# MCU.net
KiCad netlist of a schematic drawn in Altium Designer
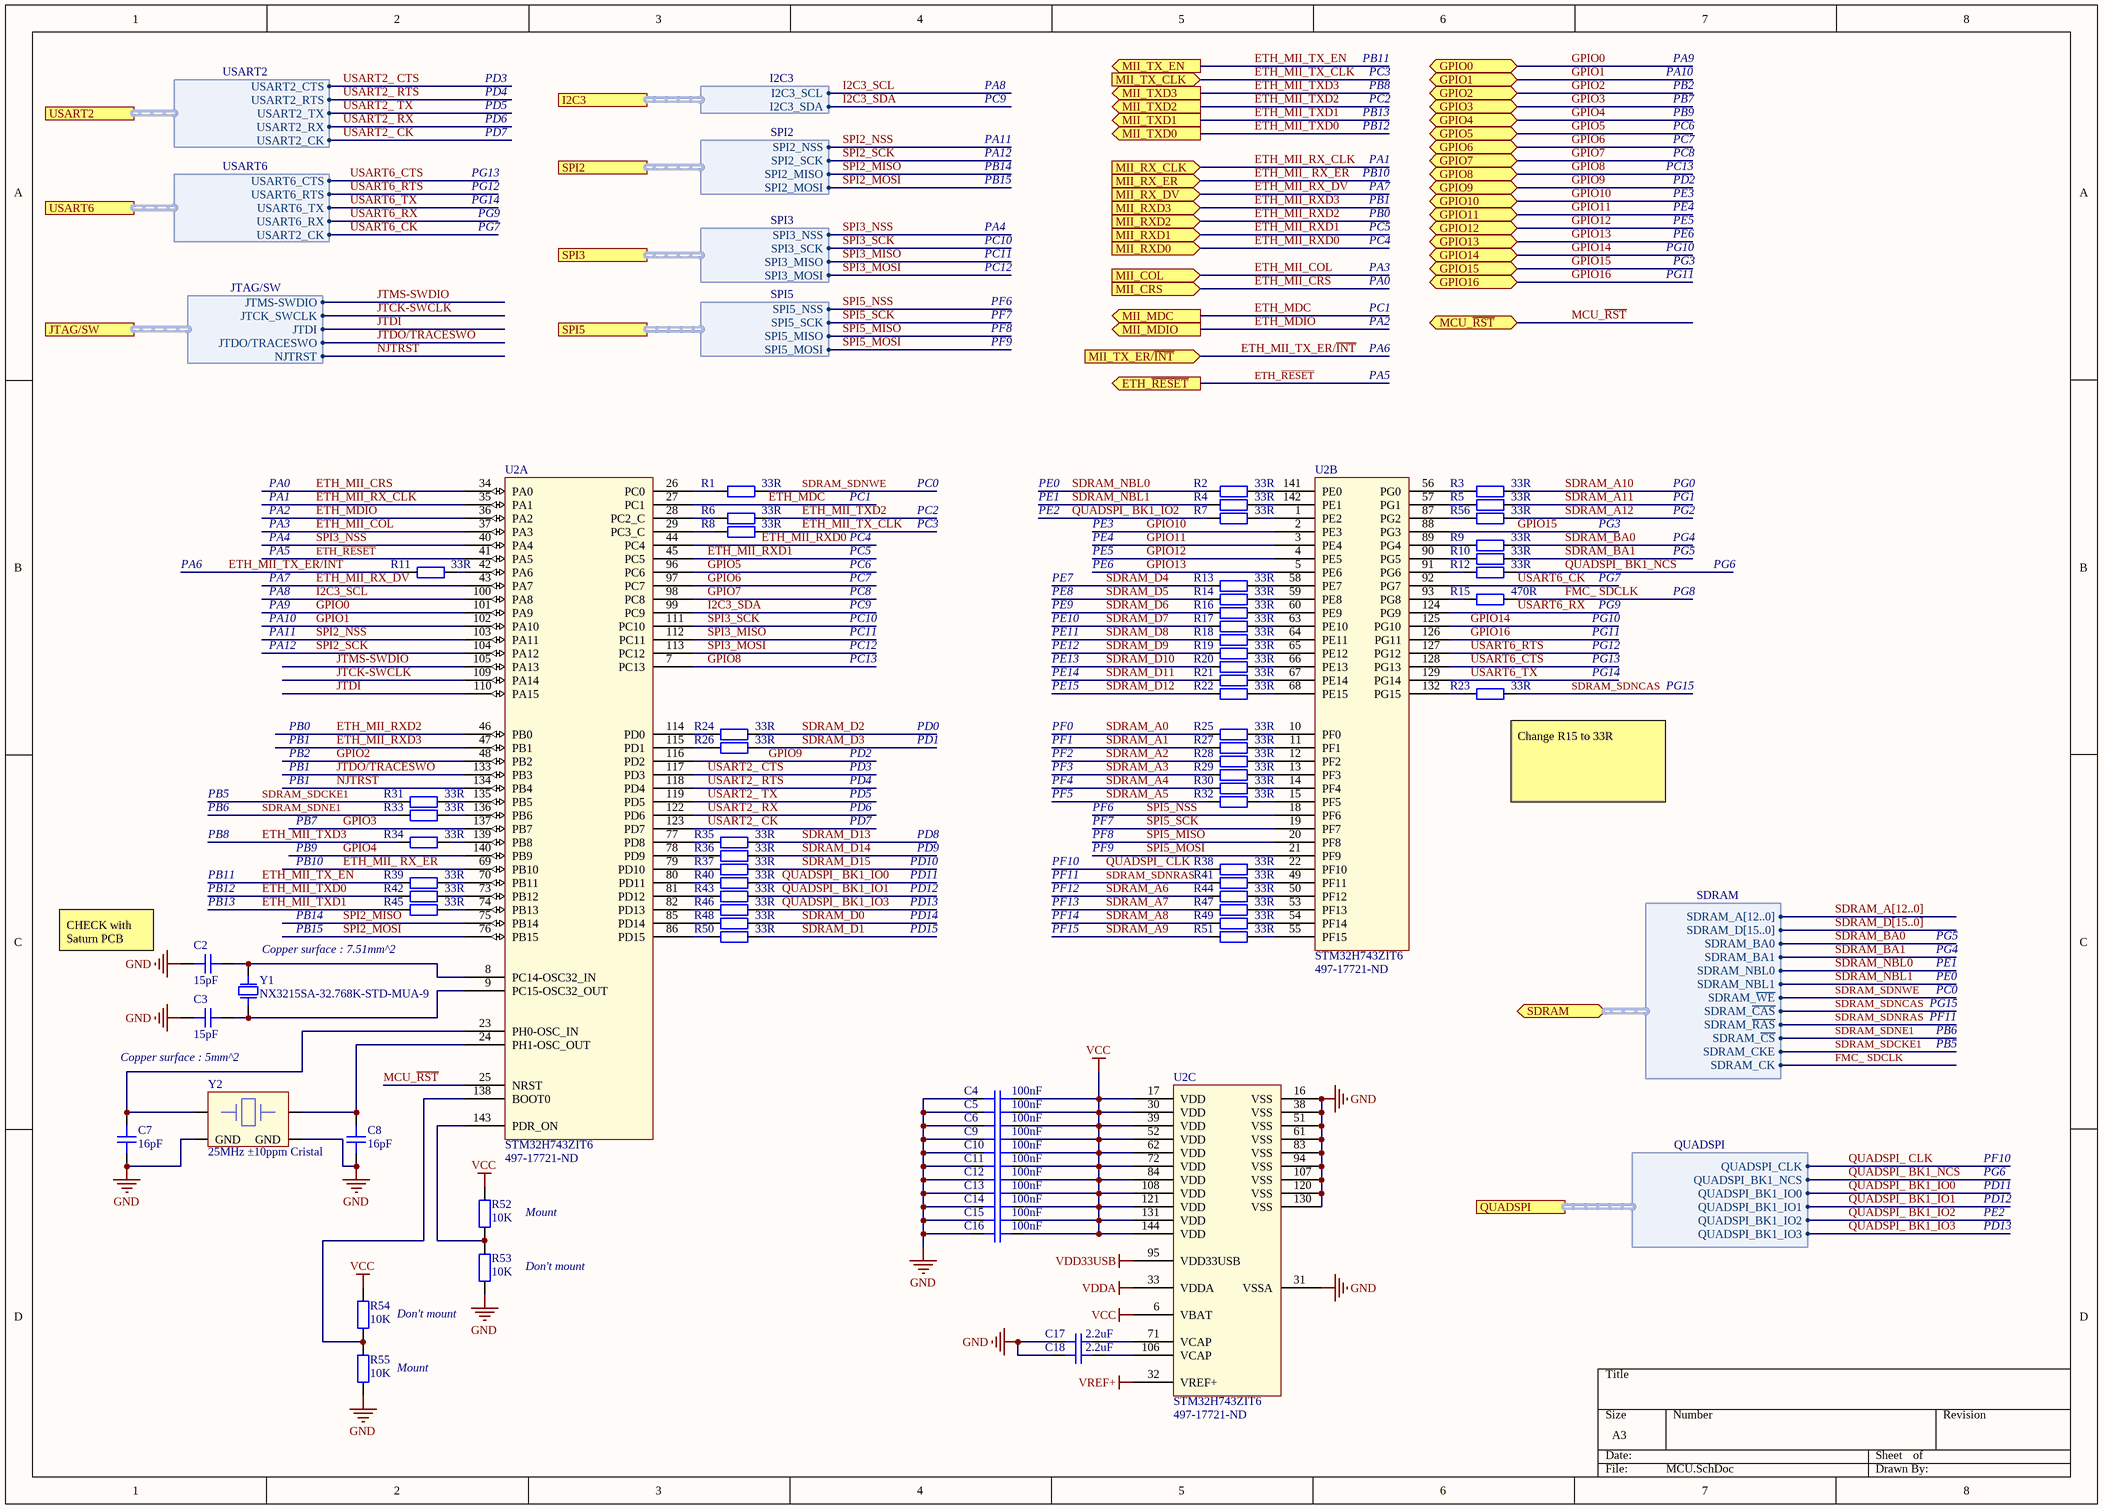
[diagram p0: MCU.SchDoc]

(export (version "E")
  (design (tool "Eeschema 10.0.6"))
  (components
    (comp (ref "C2")
      (value "15pF")
      (footprint "Capacitor-0603")
      (fields (field (name "Comment") "C-15pF-0603"))
      (libsource (lib "Components") (part "C-15pF-0603"))
    )
    (comp (ref "C3")
      (value "15pF")
      (footprint "Capacitor-0603")
      (fields (field (name "Comment") "C-15pF-0603"))
      (libsource (lib "Components") (part "C-15pF-0603"))
    )
    (comp (ref "C4")
      (value "100nF")
      (footprint "Capacitor-0603")
      (fields (field (name "Comment") "C-100nF-0603"))
      (libsource (lib "Components") (part "C-100nF-0603"))
    )
    (comp (ref "C5")
      (value "100nF")
      (footprint "Capacitor-0603")
      (fields (field (name "Comment") "C-100nF-0603"))
      (libsource (lib "Components") (part "C-100nF-0603"))
    )
    (comp (ref "C6")
      (value "100nF")
      (footprint "Capacitor-0603")
      (fields (field (name "Comment") "C-100nF-0603"))
      (libsource (lib "Components") (part "C-100nF-0603"))
    )
    (comp (ref "C7")
      (value "16pF")
      (footprint "Capacitor-0603")
      (fields (field (name "Comment") "C-16pF-0603"))
      (libsource (lib "Components") (part "C-16pF-0603"))
    )
    (comp (ref "C8")
      (value "16pF")
      (footprint "Capacitor-0603")
      (fields (field (name "Comment") "C-16pF-0603"))
      (libsource (lib "Components") (part "C-16pF-0603"))
    )
    (comp (ref "C9")
      (value "100nF")
      (footprint "Capacitor-0603")
      (fields (field (name "Comment") "C-100nF-0603"))
      (libsource (lib "Components") (part "C-100nF-0603"))
    )
    (comp (ref "C10")
      (value "100nF")
      (footprint "Capacitor-0603")
      (fields (field (name "Comment") "C-100nF-0603"))
      (libsource (lib "Components") (part "C-100nF-0603"))
    )
    (comp (ref "C11")
      (value "100nF")
      (footprint "Capacitor-0603")
      (fields (field (name "Comment") "C-100nF-0603"))
      (libsource (lib "Components") (part "C-100nF-0603"))
    )
    (comp (ref "C12")
      (value "100nF")
      (footprint "Capacitor-0603")
      (fields (field (name "Comment") "C-100nF-0603"))
      (libsource (lib "Components") (part "C-100nF-0603"))
    )
    (comp (ref "C13")
      (value "100nF")
      (footprint "Capacitor-0603")
      (fields (field (name "Comment") "C-100nF-0603"))
      (libsource (lib "Components") (part "C-100nF-0603"))
    )
    (comp (ref "C14")
      (value "100nF")
      (footprint "Capacitor-0603")
      (fields (field (name "Comment") "C-100nF-0603"))
      (libsource (lib "Components") (part "C-100nF-0603"))
    )
    (comp (ref "C15")
      (value "100nF")
      (footprint "Capacitor-0603")
      (fields (field (name "Comment") "C-100nF-0603"))
      (libsource (lib "Components") (part "C-100nF-0603"))
    )
    (comp (ref "C16")
      (value "100nF")
      (footprint "Capacitor-0603")
      (fields (field (name "Comment") "C-100nF-0603"))
      (libsource (lib "Components") (part "C-100nF-0603"))
    )
    (comp (ref "C17")
      (value "2.2uF")
      (footprint "Capacitor-0603")
      (fields (field (name "Comment") "C-2.2uF-0603"))
      (libsource (lib "Components") (part "C-2.2uF-0603"))
    )
    (comp (ref "C18")
      (value "2.2uF")
      (footprint "Capacitor-0603")
      (fields (field (name "Comment") "C-2.2uF-0603"))
      (libsource (lib "Components") (part "C-2.2uF-0603"))
    )
    (comp (ref "R1")
      (value "33R")
      (footprint "Resistor-0603")
      (fields (field (name "Comment") "R-33R-0603"))
      (libsource (lib "Components") (part "R-33R-0603"))
    )
    (comp (ref "R2")
      (value "33R")
      (footprint "Resistor-0603")
      (fields (field (name "Comment") "R-33R-0603"))
      (libsource (lib "Components") (part "R-33R-0603"))
    )
    (comp (ref "R3")
      (value "33R")
      (footprint "Resistor-0603")
      (fields (field (name "Comment") "R-33R-0603"))
      (libsource (lib "Components") (part "R-33R-0603"))
    )
    (comp (ref "R4")
      (value "33R")
      (footprint "Resistor-0603")
      (fields (field (name "Comment") "R-33R-0603"))
      (libsource (lib "Components") (part "R-33R-0603"))
    )
    (comp (ref "R5")
      (value "33R")
      (footprint "Resistor-0603")
      (fields (field (name "Comment") "R-33R-0603"))
      (libsource (lib "Components") (part "R-33R-0603"))
    )
    (comp (ref "R6")
      (value "33R")
      (footprint "Resistor-0603")
      (fields (field (name "Comment") "R-33R-0603"))
      (libsource (lib "Components") (part "R-33R-0603"))
    )
    (comp (ref "R7")
      (value "33R")
      (footprint "Resistor-0603")
      (fields (field (name "Comment") "R-33R-0603"))
      (libsource (lib "Components") (part "R-33R-0603"))
    )
    (comp (ref "R8")
      (value "33R")
      (footprint "Resistor-0603")
      (fields (field (name "Comment") "R-33R-0603"))
      (libsource (lib "Components") (part "R-33R-0603"))
    )
    (comp (ref "R9")
      (value "33R")
      (footprint "Resistor-0603")
      (fields (field (name "Comment") "R-33R-0603"))
      (libsource (lib "Components") (part "R-33R-0603"))
    )
    (comp (ref "R10")
      (value "33R")
      (footprint "Resistor-0603")
      (fields (field (name "Comment") "R-33R-0603"))
      (libsource (lib "Components") (part "R-33R-0603"))
    )
    (comp (ref "R11")
      (value "33R")
      (footprint "Resistor-0603")
      (fields (field (name "Comment") "R-33R-0603"))
      (libsource (lib "Components") (part "R-33R-0603"))
    )
    (comp (ref "R12")
      (value "33R")
      (footprint "Resistor-0603")
      (fields (field (name "Comment") "R-33R-0603"))
      (libsource (lib "Components") (part "R-33R-0603"))
    )
    (comp (ref "R13")
      (value "33R")
      (footprint "Resistor-0603")
      (fields (field (name "Comment") "R-33R-0603"))
      (libsource (lib "Components") (part "R-33R-0603"))
    )
    (comp (ref "R14")
      (value "33R")
      (footprint "Resistor-0603")
      (fields (field (name "Comment") "R-33R-0603"))
      (libsource (lib "Components") (part "R-33R-0603"))
    )
    (comp (ref "R15")
      (value "470R")
      (footprint "Resistor-0603")
      (fields (field (name "Comment") "R-470R-0603"))
      (libsource (lib "Components") (part "R-470R-0603"))
    )
    (comp (ref "R16")
      (value "33R")
      (footprint "Resistor-0603")
      (fields (field (name "Comment") "R-33R-0603"))
      (libsource (lib "Components") (part "R-33R-0603"))
    )
    (comp (ref "R17")
      (value "33R")
      (footprint "Resistor-0603")
      (fields (field (name "Comment") "R-33R-0603"))
      (libsource (lib "Components") (part "R-33R-0603"))
    )
    (comp (ref "R18")
      (value "33R")
      (footprint "Resistor-0603")
      (fields (field (name "Comment") "R-33R-0603"))
      (libsource (lib "Components") (part "R-33R-0603"))
    )
    (comp (ref "R19")
      (value "33R")
      (footprint "Resistor-0603")
      (fields (field (name "Comment") "R-33R-0603"))
      (libsource (lib "Components") (part "R-33R-0603"))
    )
    (comp (ref "R20")
      (value "33R")
      (footprint "Resistor-0603")
      (fields (field (name "Comment") "R-33R-0603"))
      (libsource (lib "Components") (part "R-33R-0603"))
    )
    (comp (ref "R21")
      (value "33R")
      (footprint "Resistor-0603")
      (fields (field (name "Comment") "R-33R-0603"))
      (libsource (lib "Components") (part "R-33R-0603"))
    )
    (comp (ref "R22")
      (value "33R")
      (footprint "Resistor-0603")
      (fields (field (name "Comment") "R-33R-0603"))
      (libsource (lib "Components") (part "R-33R-0603"))
    )
    (comp (ref "R23")
      (value "33R")
      (footprint "Resistor-0603")
      (fields (field (name "Comment") "R-33R-0603"))
      (libsource (lib "Components") (part "R-33R-0603"))
    )
    (comp (ref "R24")
      (value "33R")
      (footprint "Resistor-0603")
      (fields (field (name "Comment") "R-33R-0603"))
      (libsource (lib "Components") (part "R-33R-0603"))
    )
    (comp (ref "R25")
      (value "33R")
      (footprint "Resistor-0603")
      (fields (field (name "Comment") "R-33R-0603"))
      (libsource (lib "Components") (part "R-33R-0603"))
    )
    (comp (ref "R26")
      (value "33R")
      (footprint "Resistor-0603")
      (fields (field (name "Comment") "R-33R-0603"))
      (libsource (lib "Components") (part "R-33R-0603"))
    )
    (comp (ref "R27")
      (value "33R")
      (footprint "Resistor-0603")
      (fields (field (name "Comment") "R-33R-0603"))
      (libsource (lib "Components") (part "R-33R-0603"))
    )
    (comp (ref "R28")
      (value "33R")
      (footprint "Resistor-0603")
      (fields (field (name "Comment") "R-33R-0603"))
      (libsource (lib "Components") (part "R-33R-0603"))
    )
    (comp (ref "R29")
      (value "33R")
      (footprint "Resistor-0603")
      (fields (field (name "Comment") "R-33R-0603"))
      (libsource (lib "Components") (part "R-33R-0603"))
    )
    (comp (ref "R30")
      (value "33R")
      (footprint "Resistor-0603")
      (fields (field (name "Comment") "R-33R-0603"))
      (libsource (lib "Components") (part "R-33R-0603"))
    )
    (comp (ref "R31")
      (value "33R")
      (footprint "Resistor-0603")
      (fields (field (name "Comment") "R-33R-0603"))
      (libsource (lib "Components") (part "R-33R-0603"))
    )
    (comp (ref "R32")
      (value "33R")
      (footprint "Resistor-0603")
      (fields (field (name "Comment") "R-33R-0603"))
      (libsource (lib "Components") (part "R-33R-0603"))
    )
    (comp (ref "R33")
      (value "33R")
      (footprint "Resistor-0603")
      (fields (field (name "Comment") "R-33R-0603"))
      (libsource (lib "Components") (part "R-33R-0603"))
    )
    (comp (ref "R34")
      (value "33R")
      (footprint "Resistor-0603")
      (fields (field (name "Comment") "R-33R-0603"))
      (libsource (lib "Components") (part "R-33R-0603"))
    )
    (comp (ref "R35")
      (value "33R")
      (footprint "Resistor-0603")
      (fields (field (name "Comment") "R-33R-0603"))
      (libsource (lib "Components") (part "R-33R-0603"))
    )
    (comp (ref "R36")
      (value "33R")
      (footprint "Resistor-0603")
      (fields (field (name "Comment") "R-33R-0603"))
      (libsource (lib "Components") (part "R-33R-0603"))
    )
    (comp (ref "R37")
      (value "33R")
      (footprint "Resistor-0603")
      (fields (field (name "Comment") "R-33R-0603"))
      (libsource (lib "Components") (part "R-33R-0603"))
    )
    (comp (ref "R38")
      (value "33R")
      (footprint "Resistor-0603")
      (fields (field (name "Comment") "R-33R-0603"))
      (libsource (lib "Components") (part "R-33R-0603"))
    )
    (comp (ref "R39")
      (value "33R")
      (footprint "Resistor-0603")
      (fields (field (name "Comment") "R-33R-0603"))
      (libsource (lib "Components") (part "R-33R-0603"))
    )
    (comp (ref "R40")
      (value "33R")
      (footprint "Resistor-0603")
      (fields (field (name "Comment") "R-33R-0603"))
      (libsource (lib "Components") (part "R-33R-0603"))
    )
    (comp (ref "R41")
      (value "33R")
      (footprint "Resistor-0603")
      (fields (field (name "Comment") "R-33R-0603"))
      (libsource (lib "Components") (part "R-33R-0603"))
    )
    (comp (ref "R42")
      (value "33R")
      (footprint "Resistor-0603")
      (fields (field (name "Comment") "R-33R-0603"))
      (libsource (lib "Components") (part "R-33R-0603"))
    )
    (comp (ref "R43")
      (value "33R")
      (footprint "Resistor-0603")
      (fields (field (name "Comment") "R-33R-0603"))
      (libsource (lib "Components") (part "R-33R-0603"))
    )
    (comp (ref "R44")
      (value "33R")
      (footprint "Resistor-0603")
      (fields (field (name "Comment") "R-33R-0603"))
      (libsource (lib "Components") (part "R-33R-0603"))
    )
    (comp (ref "R45")
      (value "33R")
      (footprint "Resistor-0603")
      (fields (field (name "Comment") "R-33R-0603"))
      (libsource (lib "Components") (part "R-33R-0603"))
    )
    (comp (ref "R46")
      (value "33R")
      (footprint "Resistor-0603")
      (fields (field (name "Comment") "R-33R-0603"))
      (libsource (lib "Components") (part "R-33R-0603"))
    )
    (comp (ref "R47")
      (value "33R")
      (footprint "Resistor-0603")
      (fields (field (name "Comment") "R-33R-0603"))
      (libsource (lib "Components") (part "R-33R-0603"))
    )
    (comp (ref "R48")
      (value "33R")
      (footprint "Resistor-0603")
      (fields (field (name "Comment") "R-33R-0603"))
      (libsource (lib "Components") (part "R-33R-0603"))
    )
    (comp (ref "R49")
      (value "33R")
      (footprint "Resistor-0603")
      (fields (field (name "Comment") "R-33R-0603"))
      (libsource (lib "Components") (part "R-33R-0603"))
    )
    (comp (ref "R50")
      (value "33R")
      (footprint "Resistor-0603")
      (fields (field (name "Comment") "R-33R-0603"))
      (libsource (lib "Components") (part "R-33R-0603"))
    )
    (comp (ref "R51")
      (value "33R")
      (footprint "Resistor-0603")
      (fields (field (name "Comment") "R-33R-0603"))
      (libsource (lib "Components") (part "R-33R-0603"))
    )
    (comp (ref "R52")
      (value "10K")
      (footprint "Resistor-0603")
      (fields (field (name "Comment") "R-10K-0603"))
      (libsource (lib "Components") (part "R-10K-0603"))
    )
    (comp (ref "R53")
      (value "10K")
      (footprint "Resistor-0603")
      (fields (field (name "Comment") "R-10K-0603"))
      (libsource (lib "Components") (part "R-10K-0603"))
    )
    (comp (ref "R54")
      (value "10K")
      (footprint "Resistor-0603")
      (fields (field (name "Comment") "R-10K-0603"))
      (libsource (lib "Components") (part "R-10K-0603"))
    )
    (comp (ref "R55")
      (value "10K")
      (footprint "Resistor-0603")
      (fields (field (name "Comment") "R-10K-0603"))
      (libsource (lib "Components") (part "R-10K-0603"))
    )
    (comp (ref "R56")
      (value "33R")
      (footprint "Resistor-0603")
      (fields (field (name "Comment") "R-33R-0603"))
      (libsource (lib "Components") (part "R-33R-0603"))
    )
    (comp (ref "U2")
      (value "STM32H743ZIT6")
      (footprint "STM32H743ZIT6")
      (fields (field (name "SUPPLIER PART NUMBER 1") "497-17721-ND"))
      (libsource (lib "Components") (part "STM32H743ZIT6"))
    )
    (comp (ref "Y1")
      (value "NX3215SA-32.768K-STD-MUA-9")
      (footprint "NX3215SA-32.768K-STD-MUA-9")
      (libsource (lib "Components") (part "NX3215SA-32.768K-STD-MUA-9"))
    )
    (comp (ref "Y2")
      (value "25MHz ±10ppm Cristal")
      (footprint "830107871909")
      (libsource (lib "Components") (part "830107871909"))
    )
  )
  (nets
    (net (code "10") (name "/ETH_MDC") (class "Default")
      (node (ref "U2") (pin "27") (pinfunction "PC1_27") (pintype "passive"))
    )
    (net (code "11") (name "/ETH_MDIO") (class "Default")
      (node (ref "U2") (pin "36") (pinfunction "PA2_36") (pintype "bidirectional"))
    )
    (net (code "12") (name "/ETH_MII_ RX_ER") (class "Default")
      (node (ref "U2") (pin "69") (pinfunction "PB10_69") (pintype "bidirectional"))
    )
    (net (code "13") (name "/ETH_MII_COL") (class "Default")
      (node (ref "U2") (pin "37") (pinfunction "PA3_37") (pintype "bidirectional"))
    )
    (net (code "14") (name "/ETH_MII_CRS") (class "Default")
      (node (ref "U2") (pin "34") (pinfunction "PA0_34") (pintype "bidirectional"))
    )
    (net (code "15") (name "/ETH_MII_RXD0") (class "Default")
      (node (ref "U2") (pin "44") (pinfunction "PC4_44") (pintype "passive"))
    )
    (net (code "16") (name "/ETH_MII_RXD1") (class "Default")
      (node (ref "U2") (pin "45") (pinfunction "PC5_45") (pintype "passive"))
    )
    (net (code "17") (name "/ETH_MII_RXD2") (class "Default")
      (node (ref "U2") (pin "46") (pinfunction "PB0_46") (pintype "bidirectional"))
    )
    (net (code "18") (name "/ETH_MII_RXD3") (class "Default")
      (node (ref "U2") (pin "47") (pinfunction "PB1_47") (pintype "bidirectional"))
    )
    (net (code "19") (name "/ETH_MII_RX_CLK") (class "Default")
      (node (ref "U2") (pin "35") (pinfunction "PA1_35") (pintype "bidirectional"))
    )
    (net (code "20") (name "/ETH_MII_RX_DV") (class "Default")
      (node (ref "U2") (pin "43") (pinfunction "PA7_43") (pintype "bidirectional"))
    )
    (net (code "21") (name "/ETH_MII_TXD0") (class "Default")
      (node (ref "R42") (pin "1") (pinfunction "1_1") (pintype "passive"))
    )
    (net (code "22") (name "/ETH_MII_TXD1") (class "Default")
      (node (ref "R45") (pin "1") (pinfunction "1_1") (pintype "passive"))
    )
    (net (code "23") (name "/ETH_MII_TXD2") (class "Default")
      (node (ref "R6") (pin "2") (pinfunction "2_2") (pintype "passive"))
    )
    (net (code "24") (name "/ETH_MII_TXD3") (class "Default")
      (node (ref "R34") (pin "1") (pinfunction "1_1") (pintype "passive"))
    )
    (net (code "25") (name "/ETH_MII_TX_CLK") (class "Default")
      (node (ref "R8") (pin "2") (pinfunction "2_2") (pintype "passive"))
    )
    (net (code "26") (name "/ETH_MII_TX_EN") (class "Default")
      (node (ref "R39") (pin "1") (pinfunction "1_1") (pintype "passive"))
    )
    (net (code "27") (name "/ETH_MII_TX_ER{slash}~{INT}") (class "Default")
      (node (ref "R11") (pin "1") (pinfunction "1_1") (pintype "passive"))
    )
    (net (code "28") (name "/ETH_~{RESET}") (class "Default")
      (node (ref "U2") (pin "41") (pinfunction "PA5_41") (pintype "bidirectional"))
    )
    (net (code "29") (name "/FMC_ SDCLK") (class "Default")
      (node (ref "R15") (pin "2") (pinfunction "2_2") (pintype "passive"))
    )
    (net (code "30") (name "/GPIO0") (class "Default")
      (node (ref "U2") (pin "101") (pinfunction "PA9_101") (pintype "bidirectional"))
    )
    (net (code "31") (name "/GPIO1") (class "Default")
      (node (ref "U2") (pin "102") (pinfunction "PA10_102") (pintype "bidirectional"))
    )
    (net (code "32") (name "/GPIO2") (class "Default")
      (node (ref "U2") (pin "48") (pinfunction "PB2_48") (pintype "bidirectional"))
    )
    (net (code "33") (name "/GPIO3") (class "Default")
      (node (ref "U2") (pin "137") (pinfunction "PB7_137") (pintype "bidirectional"))
    )
    (net (code "34") (name "/GPIO4") (class "Default")
      (node (ref "U2") (pin "140") (pinfunction "PB9_140") (pintype "bidirectional"))
    )
    (net (code "35") (name "/GPIO5") (class "Default")
      (node (ref "U2") (pin "96") (pinfunction "PC6_96") (pintype "passive"))
    )
    (net (code "36") (name "/GPIO6") (class "Default")
      (node (ref "U2") (pin "97") (pinfunction "PC7_97") (pintype "passive"))
    )
    (net (code "37") (name "/GPIO7") (class "Default")
      (node (ref "U2") (pin "98") (pinfunction "PC8_98") (pintype "passive"))
    )
    (net (code "38") (name "/GPIO8") (class "Default")
      (node (ref "U2") (pin "7") (pinfunction "PC13_7") (pintype "passive"))
    )
    (net (code "39") (name "/GPIO9") (class "Default")
      (node (ref "U2") (pin "116") (pinfunction "PD2_116") (pintype "passive"))
    )
    (net (code "40") (name "/GPIO10") (class "Default")
      (node (ref "U2") (pin "2") (pinfunction "PE3_2") (pintype "passive"))
    )
    (net (code "41") (name "/GPIO11") (class "Default")
      (node (ref "U2") (pin "3") (pinfunction "PE4_3") (pintype "passive"))
    )
    (net (code "42") (name "/GPIO12") (class "Default")
      (node (ref "U2") (pin "4") (pinfunction "PE5_4") (pintype "passive"))
    )
    (net (code "43") (name "/GPIO13") (class "Default")
      (node (ref "U2") (pin "5") (pinfunction "PE6_5") (pintype "passive"))
    )
    (net (code "44") (name "/GPIO14") (class "Default")
      (node (ref "U2") (pin "125") (pinfunction "PG10_125") (pintype "passive"))
    )
    (net (code "45") (name "/GPIO15") (class "Default")
      (node (ref "U2") (pin "88") (pinfunction "PG3_88") (pintype "passive"))
    )
    (net (code "46") (name "/GPIO16") (class "Default")
      (node (ref "U2") (pin "126") (pinfunction "PG11_126") (pintype "passive"))
    )
    (net (code "47") (name "/I2C3_SCL") (class "Default")
      (node (ref "U2") (pin "100") (pinfunction "PA8_100") (pintype "bidirectional"))
    )
    (net (code "48") (name "/I2C3_SDA") (class "Default")
      (node (ref "U2") (pin "99") (pinfunction "PC9_99") (pintype "passive"))
    )
    (net (code "49") (name "/JTCK-SWCLK") (class "Default")
      (node (ref "U2") (pin "109") (pinfunction "PA14_109") (pintype "bidirectional"))
    )
    (net (code "50") (name "/JTDI") (class "Default")
      (node (ref "U2") (pin "110") (pinfunction "PA15_110") (pintype "bidirectional"))
    )
    (net (code "51") (name "/JTDO{slash}TRACESWO") (class "Default")
      (node (ref "U2") (pin "133") (pinfunction "PB3_133") (pintype "bidirectional"))
    )
    (net (code "52") (name "/JTMS-SWDIO") (class "Default")
      (node (ref "U2") (pin "105") (pinfunction "PA13_105") (pintype "bidirectional"))
    )
    (net (code "53") (name "/MCU_~{RST}") (class "Default")
      (node (ref "U2") (pin "25") (pinfunction "NRST_25") (pintype "passive"))
    )
    (net (code "54") (name "/NJTRST") (class "Default")
      (node (ref "U2") (pin "134") (pinfunction "PB4_134") (pintype "bidirectional"))
    )
    (net (code "55") (name "/QUADSPI_ BK1_IO0") (class "Default")
      (node (ref "R40") (pin "2") (pinfunction "2_2") (pintype "passive"))
    )
    (net (code "56") (name "/QUADSPI_ BK1_IO1") (class "Default")
      (node (ref "R43") (pin "2") (pinfunction "2_2") (pintype "passive"))
    )
    (net (code "57") (name "/QUADSPI_ BK1_IO2") (class "Default")
      (node (ref "R7") (pin "1") (pinfunction "1_1") (pintype "passive"))
    )
    (net (code "58") (name "/QUADSPI_ BK1_IO3") (class "Default")
      (node (ref "R46") (pin "2") (pinfunction "2_2") (pintype "passive"))
    )
    (net (code "59") (name "/QUADSPI_ BK1_NCS") (class "Default")
      (node (ref "R12") (pin "2") (pinfunction "2_2") (pintype "passive"))
    )
    (net (code "60") (name "/QUADSPI_ CLK") (class "Default")
      (node (ref "R38") (pin "1") (pinfunction "1_1") (pintype "passive"))
    )
    (net (code "61") (name "/SDRAM_A0") (class "Default")
      (node (ref "R25") (pin "1") (pinfunction "1_1") (pintype "passive"))
    )
    (net (code "62") (name "/SDRAM_A1") (class "Default")
      (node (ref "R27") (pin "1") (pinfunction "1_1") (pintype "passive"))
    )
    (net (code "63") (name "/SDRAM_A2") (class "Default")
      (node (ref "R28") (pin "1") (pinfunction "1_1") (pintype "passive"))
    )
    (net (code "64") (name "/SDRAM_A3") (class "Default")
      (node (ref "R29") (pin "1") (pinfunction "1_1") (pintype "passive"))
    )
    (net (code "65") (name "/SDRAM_A4") (class "Default")
      (node (ref "R30") (pin "1") (pinfunction "1_1") (pintype "passive"))
    )
    (net (code "66") (name "/SDRAM_A5") (class "Default")
      (node (ref "R32") (pin "1") (pinfunction "1_1") (pintype "passive"))
    )
    (net (code "67") (name "/SDRAM_A6") (class "Default")
      (node (ref "R44") (pin "1") (pinfunction "1_1") (pintype "passive"))
    )
    (net (code "68") (name "/SDRAM_A7") (class "Default")
      (node (ref "R47") (pin "1") (pinfunction "1_1") (pintype "passive"))
    )
    (net (code "69") (name "/SDRAM_A8") (class "Default")
      (node (ref "R49") (pin "1") (pinfunction "1_1") (pintype "passive"))
    )
    (net (code "70") (name "/SDRAM_A9") (class "Default")
      (node (ref "R51") (pin "1") (pinfunction "1_1") (pintype "passive"))
    )
    (net (code "71") (name "/SDRAM_A10") (class "Default")
      (node (ref "R3") (pin "2") (pinfunction "2_2") (pintype "passive"))
    )
    (net (code "72") (name "/SDRAM_A11") (class "Default")
      (node (ref "R5") (pin "2") (pinfunction "2_2") (pintype "passive"))
    )
    (net (code "73") (name "/SDRAM_A12") (class "Default")
      (node (ref "R56") (pin "2") (pinfunction "2_2") (pintype "passive"))
    )
    (net (code "75") (name "/SDRAM_BA0") (class "Default")
      (node (ref "R9") (pin "2") (pinfunction "2_2") (pintype "passive"))
    )
    (net (code "76") (name "/SDRAM_BA1") (class "Default")
      (node (ref "R10") (pin "2") (pinfunction "2_2") (pintype "passive"))
    )
    (net (code "77") (name "/SDRAM_D0") (class "Default")
      (node (ref "R48") (pin "2") (pinfunction "2_2") (pintype "passive"))
    )
    (net (code "78") (name "/SDRAM_D1") (class "Default")
      (node (ref "R50") (pin "2") (pinfunction "2_2") (pintype "passive"))
    )
    (net (code "79") (name "/SDRAM_D2") (class "Default")
      (node (ref "R24") (pin "2") (pinfunction "2_2") (pintype "passive"))
    )
    (net (code "80") (name "/SDRAM_D3") (class "Default")
      (node (ref "R26") (pin "2") (pinfunction "2_2") (pintype "passive"))
    )
    (net (code "81") (name "/SDRAM_D4") (class "Default")
      (node (ref "R13") (pin "1") (pinfunction "1_1") (pintype "passive"))
    )
    (net (code "82") (name "/SDRAM_D5") (class "Default")
      (node (ref "R14") (pin "1") (pinfunction "1_1") (pintype "passive"))
    )
    (net (code "83") (name "/SDRAM_D6") (class "Default")
      (node (ref "R16") (pin "1") (pinfunction "1_1") (pintype "passive"))
    )
    (net (code "84") (name "/SDRAM_D7") (class "Default")
      (node (ref "R17") (pin "1") (pinfunction "1_1") (pintype "passive"))
    )
    (net (code "85") (name "/SDRAM_D8") (class "Default")
      (node (ref "R18") (pin "1") (pinfunction "1_1") (pintype "passive"))
    )
    (net (code "86") (name "/SDRAM_D9") (class "Default")
      (node (ref "R19") (pin "1") (pinfunction "1_1") (pintype "passive"))
    )
    (net (code "87") (name "/SDRAM_D10") (class "Default")
      (node (ref "R20") (pin "1") (pinfunction "1_1") (pintype "passive"))
    )
    (net (code "88") (name "/SDRAM_D11") (class "Default")
      (node (ref "R21") (pin "1") (pinfunction "1_1") (pintype "passive"))
    )
    (net (code "89") (name "/SDRAM_D12") (class "Default")
      (node (ref "R22") (pin "1") (pinfunction "1_1") (pintype "passive"))
    )
    (net (code "90") (name "/SDRAM_D13") (class "Default")
      (node (ref "R35") (pin "2") (pinfunction "2_2") (pintype "passive"))
    )
    (net (code "91") (name "/SDRAM_D14") (class "Default")
      (node (ref "R36") (pin "2") (pinfunction "2_2") (pintype "passive"))
    )
    (net (code "92") (name "/SDRAM_D15") (class "Default")
      (node (ref "R37") (pin "2") (pinfunction "2_2") (pintype "passive"))
    )
    (net (code "94") (name "/SDRAM_NBL0") (class "Default")
      (node (ref "R2") (pin "1") (pinfunction "1_1") (pintype "passive"))
    )
    (net (code "95") (name "/SDRAM_NBL1") (class "Default")
      (node (ref "R4") (pin "1") (pinfunction "1_1") (pintype "passive"))
    )
    (net (code "96") (name "/SDRAM_SDCKE1") (class "Default")
      (node (ref "R31") (pin "1") (pinfunction "1_1") (pintype "passive"))
    )
    (net (code "97") (name "/SDRAM_SDNCAS") (class "Default")
      (node (ref "R23") (pin "2") (pinfunction "2_2") (pintype "passive"))
    )
    (net (code "98") (name "/SDRAM_SDNE1") (class "Default")
      (node (ref "R33") (pin "1") (pinfunction "1_1") (pintype "passive"))
    )
    (net (code "99") (name "/SDRAM_SDNRAS") (class "Default")
      (node (ref "R41") (pin "1") (pinfunction "1_1") (pintype "passive"))
    )
    (net (code "100") (name "/SDRAM_SDNWE") (class "Default")
      (node (ref "R1") (pin "2") (pinfunction "2_2") (pintype "passive"))
    )
    (net (code "101") (name "/SPI2_MISO") (class "Default")
      (node (ref "U2") (pin "75") (pinfunction "PB14_75") (pintype "bidirectional"))
    )
    (net (code "102") (name "/SPI2_MOSI") (class "Default")
      (node (ref "U2") (pin "76") (pinfunction "PB15_76") (pintype "bidirectional"))
    )
    (net (code "103") (name "/SPI2_NSS") (class "Default")
      (node (ref "U2") (pin "103") (pinfunction "PA11_103") (pintype "bidirectional"))
    )
    (net (code "104") (name "/SPI2_SCK") (class "Default")
      (node (ref "U2") (pin "104") (pinfunction "PA12_104") (pintype "bidirectional"))
    )
    (net (code "105") (name "/SPI3_MISO") (class "Default")
      (node (ref "U2") (pin "112") (pinfunction "PC11_112") (pintype "passive"))
    )
    (net (code "106") (name "/SPI3_MOSI") (class "Default")
      (node (ref "U2") (pin "113") (pinfunction "PC12_113") (pintype "passive"))
    )
    (net (code "107") (name "/SPI3_NSS") (class "Default")
      (node (ref "U2") (pin "40") (pinfunction "PA4_40") (pintype "bidirectional"))
    )
    (net (code "108") (name "/SPI3_SCK") (class "Default")
      (node (ref "U2") (pin "111") (pinfunction "PC10_111") (pintype "passive"))
    )
    (net (code "109") (name "/SPI5_MISO") (class "Default")
      (node (ref "U2") (pin "20") (pinfunction "PF8_20") (pintype "passive"))
    )
    (net (code "110") (name "/SPI5_MOSI") (class "Default")
      (node (ref "U2") (pin "21") (pinfunction "PF9_21") (pintype "passive"))
    )
    (net (code "111") (name "/SPI5_NSS") (class "Default")
      (node (ref "U2") (pin "18") (pinfunction "PF6_18") (pintype "passive"))
    )
    (net (code "112") (name "/SPI5_SCK") (class "Default")
      (node (ref "U2") (pin "19") (pinfunction "PF7_19") (pintype "passive"))
    )
    (net (code "113") (name "/USART2_ CK") (class "Default")
      (node (ref "U2") (pin "123") (pinfunction "PD7_123") (pintype "passive"))
    )
    (net (code "114") (name "/USART2_ CTS") (class "Default")
      (node (ref "U2") (pin "117") (pinfunction "PD3_117") (pintype "passive"))
    )
    (net (code "115") (name "/USART2_ RTS") (class "Default")
      (node (ref "U2") (pin "118") (pinfunction "PD4_118") (pintype "passive"))
    )
    (net (code "116") (name "/USART2_ RX") (class "Default")
      (node (ref "U2") (pin "122") (pinfunction "PD6_122") (pintype "passive"))
    )
    (net (code "117") (name "/USART2_ TX") (class "Default")
      (node (ref "U2") (pin "119") (pinfunction "PD5_119") (pintype "passive"))
    )
    (net (code "118") (name "/USART6_CK") (class "Default")
      (node (ref "U2") (pin "92") (pinfunction "PG7_92") (pintype "passive"))
    )
    (net (code "119") (name "/USART6_CTS") (class "Default")
      (node (ref "U2") (pin "128") (pinfunction "PG13_128") (pintype "passive"))
    )
    (net (code "120") (name "/USART6_RTS") (class "Default")
      (node (ref "U2") (pin "127") (pinfunction "PG12_127") (pintype "passive"))
    )
    (net (code "121") (name "/USART6_RX") (class "Default")
      (node (ref "U2") (pin "124") (pinfunction "PG9_124") (pintype "passive"))
    )
    (net (code "122") (name "/USART6_TX") (class "Default")
      (node (ref "U2") (pin "129") (pinfunction "PG14_129") (pintype "passive"))
    )
    (net (code "132") (name "GND") (class "Default")
      (node (ref "C10") (pin "1") (pinfunction "1_1") (pintype "passive"))
      (node (ref "C11") (pin "1") (pinfunction "1_1") (pintype "passive"))
      (node (ref "C12") (pin "1") (pinfunction "1_1") (pintype "passive"))
      (node (ref "C13") (pin "1") (pinfunction "1_1") (pintype "passive"))
      (node (ref "C14") (pin "1") (pinfunction "1_1") (pintype "passive"))
      (node (ref "C15") (pin "1") (pinfunction "1_1") (pintype "passive"))
      (node (ref "C16") (pin "1") (pinfunction "1_1") (pintype "passive"))
      (node (ref "C17") (pin "1") (pinfunction "1_1") (pintype "passive"))
      (node (ref "C18") (pin "1") (pinfunction "1_1") (pintype "passive"))
      (node (ref "C2") (pin "1") (pinfunction "1_1") (pintype "passive"))
      (node (ref "C3") (pin "1") (pinfunction "1_1") (pintype "passive"))
      (node (ref "C4") (pin "1") (pinfunction "1_1") (pintype "passive"))
      (node (ref "C5") (pin "1") (pinfunction "1_1") (pintype "passive"))
      (node (ref "C6") (pin "1") (pinfunction "1_1") (pintype "passive"))
      (node (ref "C7") (pin "1") (pinfunction "1_1") (pintype "passive"))
      (node (ref "C8") (pin "1") (pinfunction "1_1") (pintype "passive"))
      (node (ref "C9") (pin "1") (pinfunction "1_1") (pintype "passive"))
      (node (ref "R53") (pin "1") (pinfunction "1_1") (pintype "passive"))
      (node (ref "R55") (pin "1") (pinfunction "1_1") (pintype "passive"))
      (node (ref "U2") (pin "107") (pinfunction "VSS_107") (pintype "passive"))
      (node (ref "U2") (pin "120") (pinfunction "VSS_120") (pintype "passive"))
      (node (ref "U2") (pin "130") (pinfunction "VSS_130") (pintype "passive"))
      (node (ref "U2") (pin "16") (pinfunction "VSS_16") (pintype "passive"))
      (node (ref "U2") (pin "31") (pinfunction "VSSA_31") (pintype "passive"))
      (node (ref "U2") (pin "38") (pinfunction "VSS_38") (pintype "passive"))
      (node (ref "U2") (pin "51") (pinfunction "VSS_51") (pintype "passive"))
      (node (ref "U2") (pin "61") (pinfunction "VSS_61") (pintype "passive"))
      (node (ref "U2") (pin "83") (pinfunction "VSS_83") (pintype "passive"))
      (node (ref "U2") (pin "94") (pinfunction "VSS_94") (pintype "passive"))
      (node (ref "Y2") (pin "2") (pinfunction "GND_2") (pintype "passive"))
      (node (ref "Y2") (pin "4") (pinfunction "GND_4") (pintype "passive"))
    )
    (net (code "133") (name "Net-(C17-Pad2)") (class "Default")
      (node (ref "C17") (pin "2") (pinfunction "2_2") (pintype "passive"))
      (node (ref "U2") (pin "71") (pinfunction "VCAP_71") (pintype "passive"))
    )
    (net (code "134") (name "Net-(C18-Pad2)") (class "Default")
      (node (ref "C18") (pin "2") (pinfunction "2_2") (pintype "passive"))
      (node (ref "U2") (pin "106") (pinfunction "VCAP_106") (pintype "passive"))
    )
    (net (code "135") (name "Net-(U2A-BOOT0)") (class "Default")
      (node (ref "R54") (pin "1") (pinfunction "1_1") (pintype "passive"))
      (node (ref "R55") (pin "2") (pinfunction "2_2") (pintype "passive"))
      (node (ref "U2") (pin "138") (pinfunction "BOOT0_138") (pintype "passive"))
    )
    (net (code "136") (name "Net-(U2A-PA6)") (class "Default")
      (node (ref "R11") (pin "2") (pinfunction "2_2") (pintype "passive"))
      (node (ref "U2") (pin "42") (pinfunction "PA6_42") (pintype "bidirectional"))
    )
    (net (code "137") (name "Net-(U2A-PB5)") (class "Default")
      (node (ref "R31") (pin "2") (pinfunction "2_2") (pintype "passive"))
      (node (ref "U2") (pin "135") (pinfunction "PB5_135") (pintype "bidirectional"))
    )
    (net (code "138") (name "Net-(U2A-PB6)") (class "Default")
      (node (ref "R33") (pin "2") (pinfunction "2_2") (pintype "passive"))
      (node (ref "U2") (pin "136") (pinfunction "PB6_136") (pintype "bidirectional"))
    )
    (net (code "139") (name "Net-(U2A-PB8)") (class "Default")
      (node (ref "R34") (pin "2") (pinfunction "2_2") (pintype "passive"))
      (node (ref "U2") (pin "139") (pinfunction "PB8_139") (pintype "bidirectional"))
    )
    (net (code "140") (name "Net-(U2A-PB11)") (class "Default")
      (node (ref "R39") (pin "2") (pinfunction "2_2") (pintype "passive"))
      (node (ref "U2") (pin "70") (pinfunction "PB11_70") (pintype "bidirectional"))
    )
    (net (code "141") (name "Net-(U2A-PB12)") (class "Default")
      (node (ref "R42") (pin "2") (pinfunction "2_2") (pintype "passive"))
      (node (ref "U2") (pin "73") (pinfunction "PB12_73") (pintype "bidirectional"))
    )
    (net (code "142") (name "Net-(U2A-PB13)") (class "Default")
      (node (ref "R45") (pin "2") (pinfunction "2_2") (pintype "passive"))
      (node (ref "U2") (pin "74") (pinfunction "PB13_74") (pintype "bidirectional"))
    )
    (net (code "143") (name "Net-(U2A-PC0)") (class "Default")
      (node (ref "R1") (pin "1") (pinfunction "1_1") (pintype "passive"))
      (node (ref "U2") (pin "26") (pinfunction "PC0_26") (pintype "passive"))
    )
    (net (code "144") (name "Net-(U2A-PC2_C)") (class "Default")
      (node (ref "R6") (pin "1") (pinfunction "1_1") (pintype "passive"))
      (node (ref "U2") (pin "28") (pinfunction "PC2_C_28") (pintype "passive"))
    )
    (net (code "145") (name "Net-(U2A-PC3_C)") (class "Default")
      (node (ref "R8") (pin "1") (pinfunction "1_1") (pintype "passive"))
      (node (ref "U2") (pin "29") (pinfunction "PC3_C_29") (pintype "passive"))
    )
    (net (code "146") (name "Net-(U2A-PC14-OSC32_IN)") (class "Default")
      (node (ref "C2") (pin "2") (pinfunction "2_2") (pintype "passive"))
      (node (ref "U2") (pin "8") (pinfunction "PC14-OSC32_IN_8") (pintype "passive"))
      (node (ref "Y1") (pin "2") (pinfunction "2_2") (pintype "passive"))
    )
    (net (code "147") (name "Net-(U2A-PC15-OSC32_OUT)") (class "Default")
      (node (ref "C3") (pin "2") (pinfunction "2_2") (pintype "passive"))
      (node (ref "U2") (pin "9") (pinfunction "PC15-OSC32_OUT_9") (pintype "passive"))
      (node (ref "Y1") (pin "1") (pinfunction "1_1") (pintype "passive"))
    )
    (net (code "148") (name "Net-(U2A-PD0)") (class "Default")
      (node (ref "R24") (pin "1") (pinfunction "1_1") (pintype "passive"))
      (node (ref "U2") (pin "114") (pinfunction "PD0_114") (pintype "passive"))
    )
    (net (code "149") (name "Net-(U2A-PD1)") (class "Default")
      (node (ref "R26") (pin "1") (pinfunction "1_1") (pintype "passive"))
      (node (ref "U2") (pin "115") (pinfunction "PD1_115") (pintype "passive"))
    )
    (net (code "150") (name "Net-(U2A-PD8)") (class "Default")
      (node (ref "R35") (pin "1") (pinfunction "1_1") (pintype "passive"))
      (node (ref "U2") (pin "77") (pinfunction "PD8_77") (pintype "passive"))
    )
    (net (code "151") (name "Net-(U2A-PD9)") (class "Default")
      (node (ref "R36") (pin "1") (pinfunction "1_1") (pintype "passive"))
      (node (ref "U2") (pin "78") (pinfunction "PD9_78") (pintype "passive"))
    )
    (net (code "152") (name "Net-(U2A-PD10)") (class "Default")
      (node (ref "R37") (pin "1") (pinfunction "1_1") (pintype "passive"))
      (node (ref "U2") (pin "79") (pinfunction "PD10_79") (pintype "passive"))
    )
    (net (code "153") (name "Net-(U2A-PD11)") (class "Default")
      (node (ref "R40") (pin "1") (pinfunction "1_1") (pintype "passive"))
      (node (ref "U2") (pin "80") (pinfunction "PD11_80") (pintype "passive"))
    )
    (net (code "154") (name "Net-(U2A-PD12)") (class "Default")
      (node (ref "R43") (pin "1") (pinfunction "1_1") (pintype "passive"))
      (node (ref "U2") (pin "81") (pinfunction "PD12_81") (pintype "passive"))
    )
    (net (code "155") (name "Net-(U2A-PD13)") (class "Default")
      (node (ref "R46") (pin "1") (pinfunction "1_1") (pintype "passive"))
      (node (ref "U2") (pin "82") (pinfunction "PD13_82") (pintype "passive"))
    )
    (net (code "156") (name "Net-(U2A-PD14)") (class "Default")
      (node (ref "R48") (pin "1") (pinfunction "1_1") (pintype "passive"))
      (node (ref "U2") (pin "85") (pinfunction "PD14_85") (pintype "passive"))
    )
    (net (code "157") (name "Net-(U2A-PD15)") (class "Default")
      (node (ref "R50") (pin "1") (pinfunction "1_1") (pintype "passive"))
      (node (ref "U2") (pin "86") (pinfunction "PD15_86") (pintype "passive"))
    )
    (net (code "158") (name "Net-(U2A-PDR_ON)") (class "Default")
      (node (ref "R52") (pin "1") (pinfunction "1_1") (pintype "passive"))
      (node (ref "R53") (pin "2") (pinfunction "2_2") (pintype "passive"))
      (node (ref "U2") (pin "143") (pinfunction "PDR_ON_143") (pintype "passive"))
    )
    (net (code "159") (name "Net-(U2A-PH0-OSC_IN)") (class "Default")
      (node (ref "C7") (pin "2") (pinfunction "2_2") (pintype "passive"))
      (node (ref "U2") (pin "23") (pinfunction "PH0-OSC_IN_23") (pintype "passive"))
      (node (ref "Y2") (pin "1") (pinfunction "GND_1") (pintype "passive"))
    )
    (net (code "160") (name "Net-(U2A-PH1-OSC_OUT)") (class "Default")
      (node (ref "C8") (pin "2") (pinfunction "2_2") (pintype "passive"))
      (node (ref "U2") (pin "24") (pinfunction "PH1-OSC_OUT_24") (pintype "passive"))
      (node (ref "Y2") (pin "3") (pinfunction "XTAL2_3") (pintype "passive"))
    )
    (net (code "161") (name "Net-(U2B-PE0)") (class "Default")
      (node (ref "R2") (pin "2") (pinfunction "2_2") (pintype "passive"))
      (node (ref "U2") (pin "141") (pinfunction "PE0_141") (pintype "passive"))
    )
    (net (code "162") (name "Net-(U2B-PE1)") (class "Default")
      (node (ref "R4") (pin "2") (pinfunction "2_2") (pintype "passive"))
      (node (ref "U2") (pin "142") (pinfunction "PE1_142") (pintype "passive"))
    )
    (net (code "163") (name "Net-(U2B-PE2)") (class "Default")
      (node (ref "R7") (pin "2") (pinfunction "2_2") (pintype "passive"))
      (node (ref "U2") (pin "1") (pinfunction "PE2_1") (pintype "passive"))
    )
    (net (code "164") (name "Net-(U2B-PE7)") (class "Default")
      (node (ref "R13") (pin "2") (pinfunction "2_2") (pintype "passive"))
      (node (ref "U2") (pin "58") (pinfunction "PE7_58") (pintype "passive"))
    )
    (net (code "165") (name "Net-(U2B-PE8)") (class "Default")
      (node (ref "R14") (pin "2") (pinfunction "2_2") (pintype "passive"))
      (node (ref "U2") (pin "59") (pinfunction "PE8_59") (pintype "passive"))
    )
    (net (code "166") (name "Net-(U2B-PE9)") (class "Default")
      (node (ref "R16") (pin "2") (pinfunction "2_2") (pintype "passive"))
      (node (ref "U2") (pin "60") (pinfunction "PE9_60") (pintype "passive"))
    )
    (net (code "167") (name "Net-(U2B-PE10)") (class "Default")
      (node (ref "R17") (pin "2") (pinfunction "2_2") (pintype "passive"))
      (node (ref "U2") (pin "63") (pinfunction "PE10_63") (pintype "passive"))
    )
    (net (code "168") (name "Net-(U2B-PE11)") (class "Default")
      (node (ref "R18") (pin "2") (pinfunction "2_2") (pintype "passive"))
      (node (ref "U2") (pin "64") (pinfunction "PE11_64") (pintype "passive"))
    )
    (net (code "169") (name "Net-(U2B-PE12)") (class "Default")
      (node (ref "R19") (pin "2") (pinfunction "2_2") (pintype "passive"))
      (node (ref "U2") (pin "65") (pinfunction "PE12_65") (pintype "passive"))
    )
    (net (code "170") (name "Net-(U2B-PE13)") (class "Default")
      (node (ref "R20") (pin "2") (pinfunction "2_2") (pintype "passive"))
      (node (ref "U2") (pin "66") (pinfunction "PE13_66") (pintype "passive"))
    )
    (net (code "171") (name "Net-(U2B-PE14)") (class "Default")
      (node (ref "R21") (pin "2") (pinfunction "2_2") (pintype "passive"))
      (node (ref "U2") (pin "67") (pinfunction "PE14_67") (pintype "passive"))
    )
    (net (code "172") (name "Net-(U2B-PE15)") (class "Default")
      (node (ref "R22") (pin "2") (pinfunction "2_2") (pintype "passive"))
      (node (ref "U2") (pin "68") (pinfunction "PE15_68") (pintype "passive"))
    )
    (net (code "173") (name "Net-(U2B-PF0)") (class "Default")
      (node (ref "R25") (pin "2") (pinfunction "2_2") (pintype "passive"))
      (node (ref "U2") (pin "10") (pinfunction "PF0_10") (pintype "passive"))
    )
    (net (code "174") (name "Net-(U2B-PF1)") (class "Default")
      (node (ref "R27") (pin "2") (pinfunction "2_2") (pintype "passive"))
      (node (ref "U2") (pin "11") (pinfunction "PF1_11") (pintype "passive"))
    )
    (net (code "175") (name "Net-(U2B-PF2)") (class "Default")
      (node (ref "R28") (pin "2") (pinfunction "2_2") (pintype "passive"))
      (node (ref "U2") (pin "12") (pinfunction "PF2_12") (pintype "passive"))
    )
    (net (code "176") (name "Net-(U2B-PF3)") (class "Default")
      (node (ref "R29") (pin "2") (pinfunction "2_2") (pintype "passive"))
      (node (ref "U2") (pin "13") (pinfunction "PF3_13") (pintype "passive"))
    )
    (net (code "177") (name "Net-(U2B-PF4)") (class "Default")
      (node (ref "R30") (pin "2") (pinfunction "2_2") (pintype "passive"))
      (node (ref "U2") (pin "14") (pinfunction "PF4_14") (pintype "passive"))
    )
    (net (code "178") (name "Net-(U2B-PF5)") (class "Default")
      (node (ref "R32") (pin "2") (pinfunction "2_2") (pintype "passive"))
      (node (ref "U2") (pin "15") (pinfunction "PF5_15") (pintype "passive"))
    )
    (net (code "179") (name "Net-(U2B-PF10)") (class "Default")
      (node (ref "R38") (pin "2") (pinfunction "2_2") (pintype "passive"))
      (node (ref "U2") (pin "22") (pinfunction "PF10_22") (pintype "passive"))
    )
    (net (code "180") (name "Net-(U2B-PF11)") (class "Default")
      (node (ref "R41") (pin "2") (pinfunction "2_2") (pintype "passive"))
      (node (ref "U2") (pin "49") (pinfunction "PF11_49") (pintype "passive"))
    )
    (net (code "181") (name "Net-(U2B-PF12)") (class "Default")
      (node (ref "R44") (pin "2") (pinfunction "2_2") (pintype "passive"))
      (node (ref "U2") (pin "50") (pinfunction "PF12_50") (pintype "passive"))
    )
    (net (code "182") (name "Net-(U2B-PF13)") (class "Default")
      (node (ref "R47") (pin "2") (pinfunction "2_2") (pintype "passive"))
      (node (ref "U2") (pin "53") (pinfunction "PF13_53") (pintype "passive"))
    )
    (net (code "183") (name "Net-(U2B-PF14)") (class "Default")
      (node (ref "R49") (pin "2") (pinfunction "2_2") (pintype "passive"))
      (node (ref "U2") (pin "54") (pinfunction "PF14_54") (pintype "passive"))
    )
    (net (code "184") (name "Net-(U2B-PF15)") (class "Default")
      (node (ref "R51") (pin "2") (pinfunction "2_2") (pintype "passive"))
      (node (ref "U2") (pin "55") (pinfunction "PF15_55") (pintype "passive"))
    )
    (net (code "185") (name "Net-(U2B-PG0)") (class "Default")
      (node (ref "R3") (pin "1") (pinfunction "1_1") (pintype "passive"))
      (node (ref "U2") (pin "56") (pinfunction "PG0_56") (pintype "passive"))
    )
    (net (code "186") (name "Net-(U2B-PG1)") (class "Default")
      (node (ref "R5") (pin "1") (pinfunction "1_1") (pintype "passive"))
      (node (ref "U2") (pin "57") (pinfunction "PG1_57") (pintype "passive"))
    )
    (net (code "187") (name "Net-(U2B-PG2)") (class "Default")
      (node (ref "R56") (pin "1") (pinfunction "1_1") (pintype "passive"))
      (node (ref "U2") (pin "87") (pinfunction "PG2_87") (pintype "passive"))
    )
    (net (code "188") (name "Net-(U2B-PG4)") (class "Default")
      (node (ref "R9") (pin "1") (pinfunction "1_1") (pintype "passive"))
      (node (ref "U2") (pin "89") (pinfunction "PG4_89") (pintype "passive"))
    )
    (net (code "189") (name "Net-(U2B-PG5)") (class "Default")
      (node (ref "R10") (pin "1") (pinfunction "1_1") (pintype "passive"))
      (node (ref "U2") (pin "90") (pinfunction "PG5_90") (pintype "passive"))
    )
    (net (code "190") (name "Net-(U2B-PG6)") (class "Default")
      (node (ref "R12") (pin "1") (pinfunction "1_1") (pintype "passive"))
      (node (ref "U2") (pin "91") (pinfunction "PG6_91") (pintype "passive"))
    )
    (net (code "191") (name "Net-(U2B-PG8)") (class "Default")
      (node (ref "R15") (pin "1") (pinfunction "1_1") (pintype "passive"))
      (node (ref "U2") (pin "93") (pinfunction "PG8_93") (pintype "passive"))
    )
    (net (code "192") (name "Net-(U2B-PG15)") (class "Default")
      (node (ref "R23") (pin "1") (pinfunction "1_1") (pintype "passive"))
      (node (ref "U2") (pin "132") (pinfunction "PG15_132") (pintype "passive"))
    )
    (net (code "193") (name "VCC") (class "Default")
      (node (ref "C10") (pin "2") (pinfunction "2_2") (pintype "passive"))
      (node (ref "C11") (pin "2") (pinfunction "2_2") (pintype "passive"))
      (node (ref "C12") (pin "2") (pinfunction "2_2") (pintype "passive"))
      (node (ref "C13") (pin "2") (pinfunction "2_2") (pintype "passive"))
      (node (ref "C14") (pin "2") (pinfunction "2_2") (pintype "passive"))
      (node (ref "C15") (pin "2") (pinfunction "2_2") (pintype "passive"))
      (node (ref "C16") (pin "2") (pinfunction "2_2") (pintype "passive"))
      (node (ref "C4") (pin "2") (pinfunction "2_2") (pintype "passive"))
      (node (ref "C5") (pin "2") (pinfunction "2_2") (pintype "passive"))
      (node (ref "C6") (pin "2") (pinfunction "2_2") (pintype "passive"))
      (node (ref "C9") (pin "2") (pinfunction "2_2") (pintype "passive"))
      (node (ref "R52") (pin "2") (pinfunction "2_2") (pintype "passive"))
      (node (ref "R54") (pin "2") (pinfunction "2_2") (pintype "passive"))
      (node (ref "U2") (pin "108") (pinfunction "VDD_108") (pintype "passive"))
      (node (ref "U2") (pin "121") (pinfunction "VDD_121") (pintype "passive"))
      (node (ref "U2") (pin "131") (pinfunction "VDD_131") (pintype "passive"))
      (node (ref "U2") (pin "144") (pinfunction "VDD_144") (pintype "passive"))
      (node (ref "U2") (pin "17") (pinfunction "VDD_17") (pintype "passive"))
      (node (ref "U2") (pin "30") (pinfunction "VDD_30") (pintype "passive"))
      (node (ref "U2") (pin "39") (pinfunction "VDD_39") (pintype "passive"))
      (node (ref "U2") (pin "52") (pinfunction "VDD_52") (pintype "passive"))
      (node (ref "U2") (pin "6") (pinfunction "VBAT_6") (pintype "passive"))
      (node (ref "U2") (pin "62") (pinfunction "VDD_62") (pintype "passive"))
      (node (ref "U2") (pin "72") (pinfunction "VDD_72") (pintype "passive"))
      (node (ref "U2") (pin "84") (pinfunction "VDD_84") (pintype "passive"))
    )
    (net (code "194") (name "VDD33USB") (class "Default")
      (node (ref "U2") (pin "95") (pinfunction "VDD33USB_95") (pintype "passive"))
    )
    (net (code "195") (name "VDDA") (class "Default")
      (node (ref "U2") (pin "33") (pinfunction "VDDA_33") (pintype "passive"))
    )
    (net (code "196") (name "VREF+") (class "Default")
      (node (ref "U2") (pin "32") (pinfunction "VREF+_32") (pintype "passive"))
    )
  )
)
